# ESP32_zigbee_zwave1.net
KiCad netlist of a schematic drawn in EAGLE
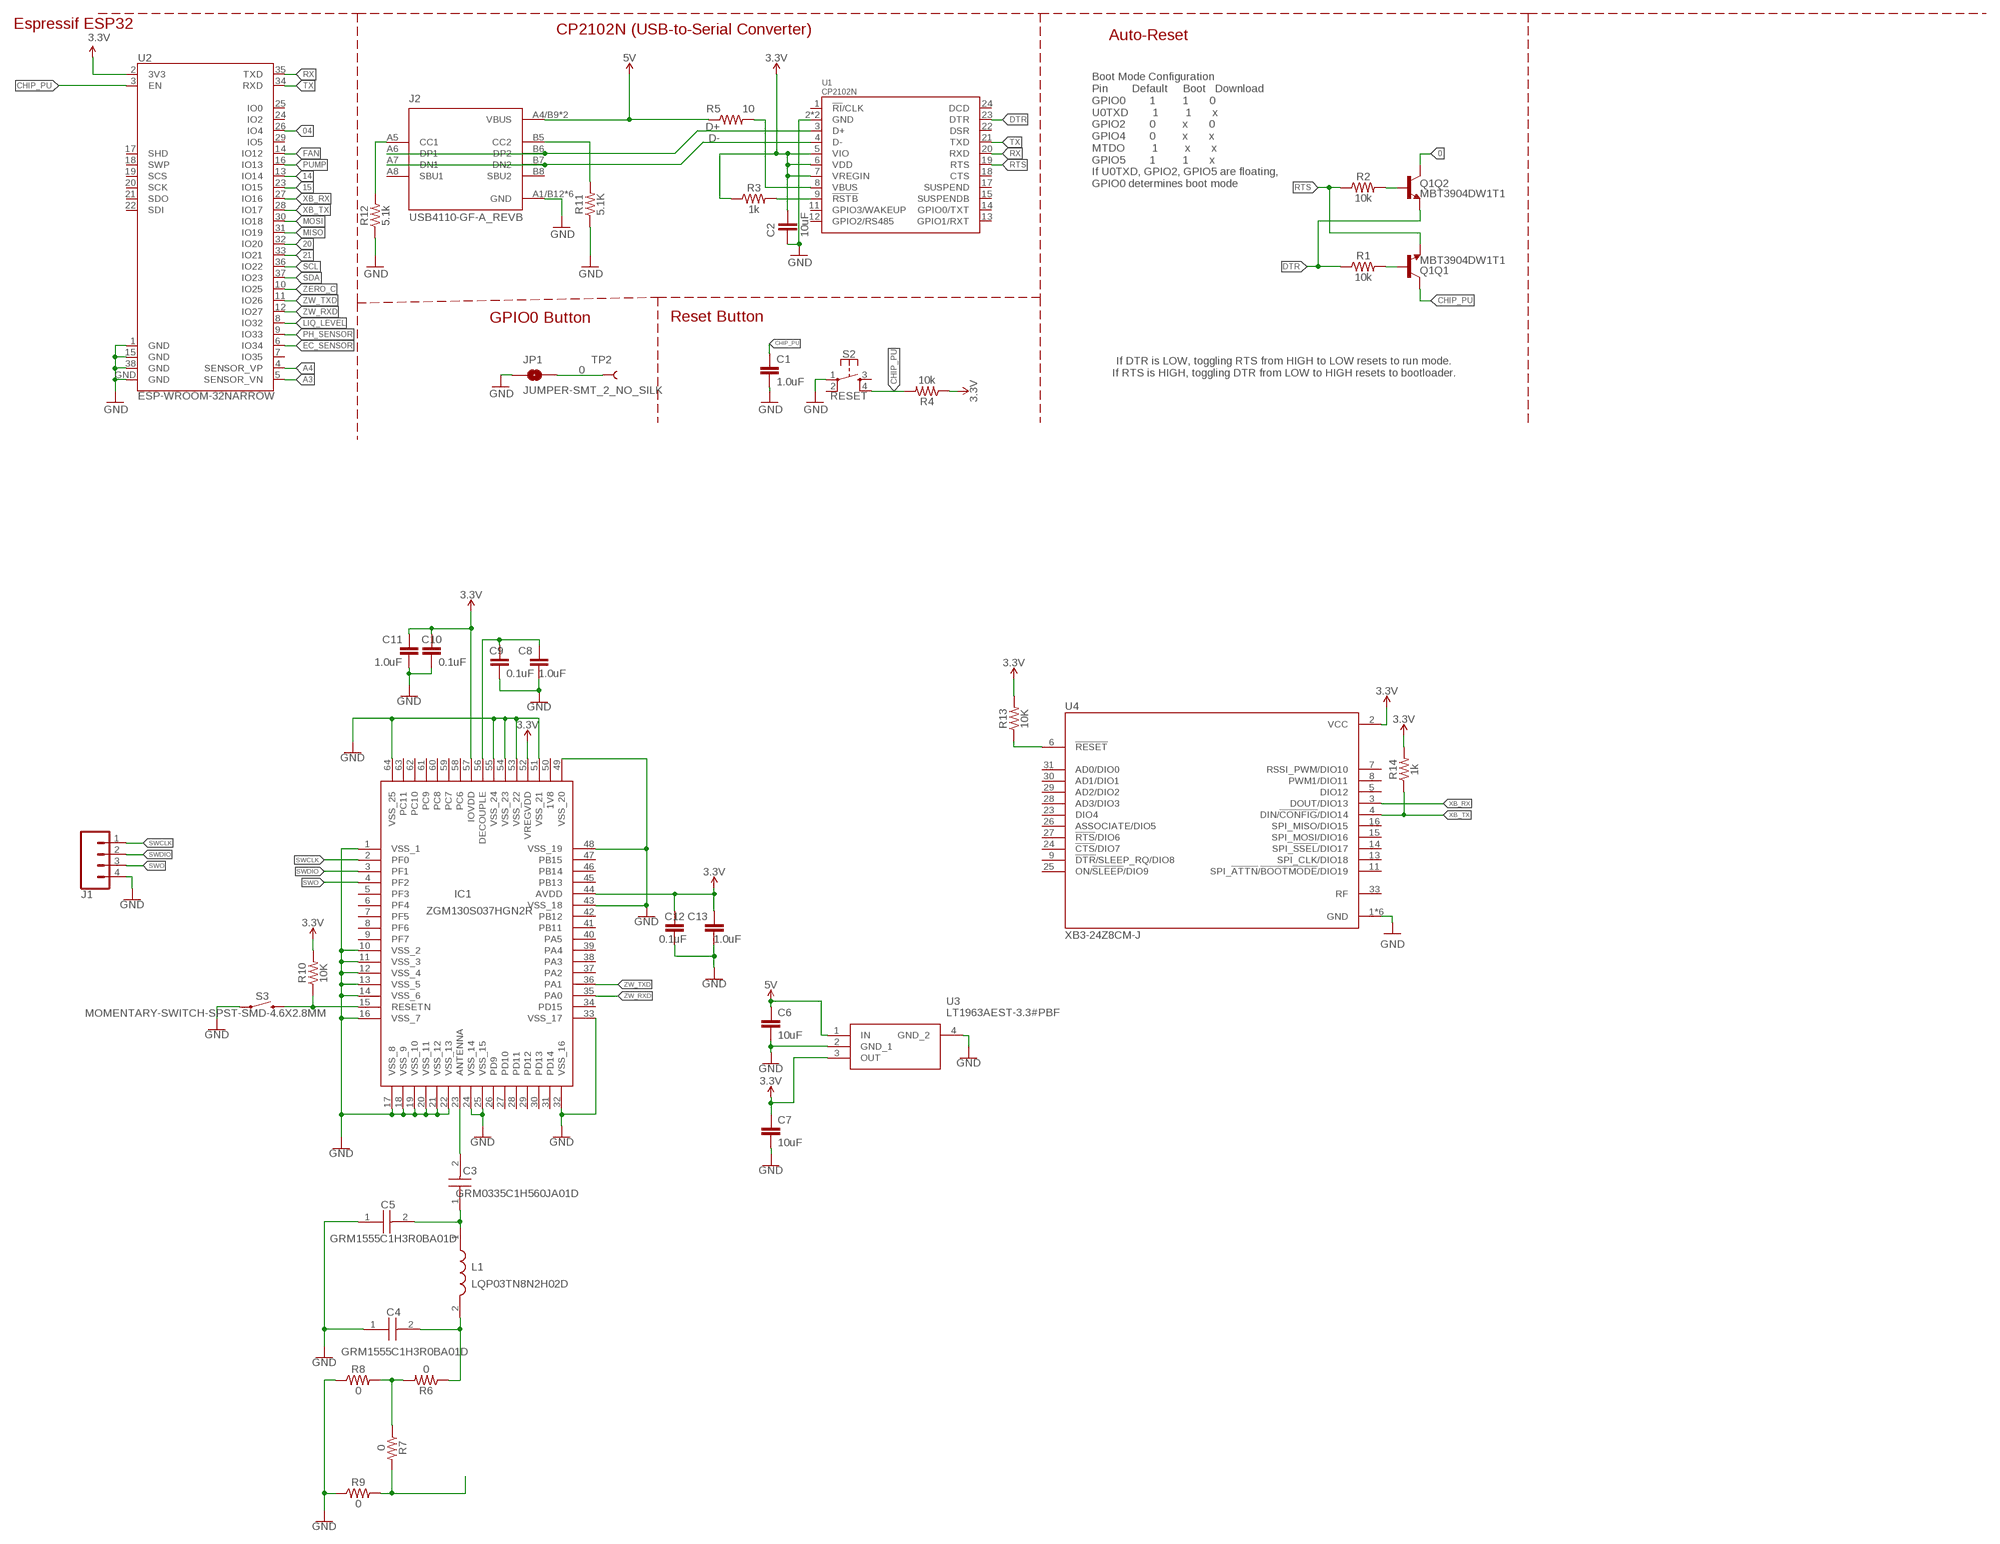
[diagram p0: schematic, sheet 1]

(export (version "E")
  (design (tool "Eeschema 10.0.6"))
  (components
    (comp (ref "C1")
      (value "1.0uF")
      (footprint "eagle-import:0402-TIGHT")
      (libsource (lib "eagle-import") (part "1.0UF-0402T-16V-10%"))
    )
    (comp (ref "C2")
      (value "10uF")
      (footprint "eagle-import:0402-TIGHT")
      (libsource (lib "eagle-import") (part "10UF-0402T-6.3V-20%"))
    )
    (comp (ref "C3")
      (value "GRM0335C1H560JA01D")
      (footprint "eagle-import:CAPC0603X33N")
      (fields (field (name "MOUSER_PART_NUMBER") "81-GRM0335C1H560JA1D"))
      (libsource (lib "eagle-import") (part "GRM0335C1H560JA01D"))
    )
    (comp (ref "C4")
      (value "GRM1555C1H3R0BA01D")
      (footprint "eagle-import:CAPC1005X55N")
      (fields (field (name "MOUSER_PART_NUMBER") "81-GRM1555C1H3R0BA1D"))
      (libsource (lib "eagle-import") (part "GRM1555C1H3R0BA01D"))
    )
    (comp (ref "C5")
      (value "GRM1555C1H3R0BA01D")
      (footprint "eagle-import:CAPC1005X55N")
      (fields (field (name "MOUSER_PART_NUMBER") "81-GRM1555C1H3R0BA1D"))
      (libsource (lib "eagle-import") (part "GRM1555C1H3R0BA01D"))
    )
    (comp (ref "C6")
      (value "10uF")
      (footprint "eagle-import:0402-TIGHT")
      (libsource (lib "eagle-import") (part "10UF-0402T-6.3V-20%"))
    )
    (comp (ref "C7")
      (value "10uF")
      (footprint "eagle-import:0402-TIGHT")
      (libsource (lib "eagle-import") (part "10UF-0402T-6.3V-20%"))
    )
    (comp (ref "C8")
      (value "1.0uF")
      (footprint "eagle-import:0402-TIGHT")
      (libsource (lib "eagle-import") (part "1.0UF-0402T-16V-10%"))
    )
    (comp (ref "C9")
      (value "0.1uF")
      (footprint "eagle-import:0402-TIGHT")
      (libsource (lib "eagle-import") (part "0.1UF-0402T-6.3V-10%-X7R"))
    )
    (comp (ref "C10")
      (value "0.1uF")
      (footprint "eagle-import:0402-TIGHT")
      (libsource (lib "eagle-import") (part "0.1UF-0402T-6.3V-10%-X7R"))
    )
    (comp (ref "C11")
      (value "1.0uF")
      (footprint "eagle-import:0402-TIGHT")
      (libsource (lib "eagle-import") (part "1.0UF-0402T-16V-10%"))
    )
    (comp (ref "C12")
      (value "0.1uF")
      (footprint "eagle-import:0402-TIGHT")
      (libsource (lib "eagle-import") (part "0.1UF-0402T-6.3V-10%-X7R"))
    )
    (comp (ref "C13")
      (value "1.0uF")
      (footprint "eagle-import:0402-TIGHT")
      (libsource (lib "eagle-import") (part "1.0UF-0402T-16V-10%"))
    )
    (comp (ref "IC1")
      (value "ZGM130S037HGN2R")
      (footprint "eagle-import:ZGM130S037HGN2R")
      (fields (field (name "MOUSER_PART_NUMBER") "634-ZGM130S037HGN2R"))
      (libsource (lib "eagle-import") (part "ZGM130S037HGN2R"))
    )
    (comp (ref "J1")
      (value "CONN_041X04_NO_SILK")
      (footprint "eagle-import:1X04_NO_SILK")
      (libsource (lib "eagle-import") (part "CONN_041X04_NO_SILK"))
    )
    (comp (ref "J2")
      (value "USB4110-GF-A_REVB")
      (footprint "eagle-import:GCT_USB4110-GF-A_REVB")
      (fields (field (name "MF") "GCT") (field (name "MP") "USB4110-GF-A"))
      (libsource (lib "eagle-import") (part "USB4110-GF-A_REVB"))
    )
    (comp (ref "JP1")
      (value "JUMPER-SMT_2_NO_SILK")
      (footprint "eagle-import:SMT-JUMPER_2_NO_SILK")
      (libsource (lib "eagle-import") (part "JUMPER-SMT_2_NO_SILK"))
    )
    (comp (ref "L1")
      (value "LQP03TN8N2H02D")
      (footprint "eagle-import:LQP03TG3N1B02D")
      (fields (field (name "MOUSER_PART_NUMBER") "81-LQP03TN8N2H02D"))
      (libsource (lib "eagle-import") (part "LQP03TN8N2H02D"))
    )
    (comp (ref "Q1")
      (value "MBT3904DW1T1")
      (footprint "eagle-import:SC70-6")
      (libsource (lib "eagle-import") (part "TRANS_NPN_DUAL-MBT3904DW1T1"))
    )
    (comp (ref "R1")
      (value "10k")
      (footprint "eagle-import:0402-TIGHT")
      (libsource (lib "eagle-import") (part "10KOHM-0402T-1/16W-1%"))
    )
    (comp (ref "R2")
      (value "10k")
      (footprint "eagle-import:0402-TIGHT")
      (libsource (lib "eagle-import") (part "10KOHM-0402T-1/16W-1%"))
    )
    (comp (ref "R3")
      (value "1k")
      (footprint "eagle-import:0402-TIGHT")
      (libsource (lib "eagle-import") (part "1KOHM-0402T-1/16W-1%"))
    )
    (comp (ref "R4")
      (value "10k")
      (footprint "eagle-import:0402-TIGHT")
      (libsource (lib "eagle-import") (part "10KOHM-0402T-1/16W-1%"))
    )
    (comp (ref "R5")
      (value "10")
      (footprint "eagle-import:0603")
      (libsource (lib "eagle-import") (part "10OHM-0603-1/10W-1%"))
    )
    (comp (ref "R6")
      (value "0")
      (footprint "eagle-import:0402-TIGHT")
      (libsource (lib "eagle-import") (part "0OHM-0402T-1/10W"))
    )
    (comp (ref "R7")
      (value "0")
      (footprint "eagle-import:0402-TIGHT")
      (libsource (lib "eagle-import") (part "0OHM-0402T-1/10W"))
    )
    (comp (ref "R8")
      (value "0")
      (footprint "eagle-import:0402-TIGHT")
      (libsource (lib "eagle-import") (part "0OHM-0402T-1/10W"))
    )
    (comp (ref "R9")
      (value "0")
      (footprint "eagle-import:0402-TIGHT")
      (libsource (lib "eagle-import") (part "0OHM-0402T-1/10W"))
    )
    (comp (ref "R10")
      (value "10K")
      (footprint "eagle-import:0402-TIGHT")
      (libsource (lib "eagle-import") (part "10KOHM-0402-1/10W-0.1%"))
    )
    (comp (ref "R11")
      (value "5.1K")
      (footprint "eagle-import:0402-TIGHT")
      (libsource (lib "eagle-import") (part "RESISTOR0402T"))
    )
    (comp (ref "R12")
      (value "5.1k")
      (footprint "eagle-import:0402-TIGHT")
      (libsource (lib "eagle-import") (part "RESISTOR0402T"))
    )
    (comp (ref "R13")
      (value "10K")
      (footprint "eagle-import:0402-TIGHT")
      (libsource (lib "eagle-import") (part "10KOHM-0402-1/10W-0.1%"))
    )
    (comp (ref "R14")
      (value "1k")
      (footprint "eagle-import:0402-TIGHT")
      (libsource (lib "eagle-import") (part "1KOHM-0402T-1/16W-1%"))
    )
    (comp (ref "S2")
      (value "RESET")
      (footprint "eagle-import:TACTILE_SWITCH_SMD_4.6X2.8MM")
      (libsource (lib "eagle-import") (part "MOMENTARY-SWITCH-SPST-2-SMD-4.6X2.8MM"))
    )
    (comp (ref "S3")
      (value "MOMENTARY-SWITCH-SPST-SMD-4.6X2.8MM")
      (footprint "eagle-import:TACTILE_SWITCH_SMD_4.6X2.8MM")
      (libsource (lib "eagle-import") (part "MOMENTARY-SWITCH-SPST-SMD-4.6X2.8MM"))
    )
    (comp (ref "TP2")
      (value "TEST-POINTTP_15TH_THRU")
      (footprint "eagle-import:TP_15TH")
      (libsource (lib "eagle-import") (part "TEST-POINTTP_15TH_THRU"))
    )
    (comp (ref "U1")
      (value "CP2102N")
      (footprint "eagle-import:QFN24")
      (libsource (lib "eagle-import") (part "CP2102N"))
    )
    (comp (ref "U2")
      (value "ESP-WROOM-32NARROW")
      (footprint "eagle-import:ESP-WROOM-32-NARROW")
      (libsource (lib "eagle-import") (part "ESP-WROOM-32NARROW"))
    )
    (comp (ref "U3")
      (value "LT1963AEST-3.3#PBF")
      (footprint "eagle-import:SOT230P700X180-4N")
      (fields (field (name "MOUSER_PART_NUMBER") "584-1963AEST-3.3PBF"))
      (libsource (lib "eagle-import") (part "LT1963AEST-3.3#PBF"))
    )
    (comp (ref "U4")
      (value "XB3-24Z8CM-J")
      (footprint "eagle-import:XCVR_XB3-24Z8CM-J")
      (fields (field (name "MF") "Digi International"))
      (libsource (lib "eagle-import") (part "XB3-24Z8CM-J"))
    )
  )
  (nets
    (net (code "1") (name "/D+") (class "Default")
      (node (ref "J2") (pin "A6") (pinfunction "DP1_A6") (pintype "bidirectional"))
      (node (ref "J2") (pin "B6") (pinfunction "DP2_B6") (pintype "bidirectional"))
      (node (ref "U1") (pin "3") (pinfunction "D+_3") (pintype "bidirectional"))
    )
    (net (code "2") (name "/D-") (class "Default")
      (node (ref "J2") (pin "A7") (pinfunction "DN1_A7") (pintype "bidirectional"))
      (node (ref "J2") (pin "B7") (pinfunction "DN2_B7") (pintype "bidirectional"))
      (node (ref "U1") (pin "4") (pinfunction "D-_4") (pintype "bidirectional"))
    )
    (net (code "3") (name "0") (class "Default")
      (node (ref "JP1") (pin "2") (pinfunction "2_2") (pintype "passive"))
      (node (ref "Q1") (pin "6") (pinfunction "C_6") (pintype "passive"))
      (node (ref "TP2") (pin "P$1") (pinfunction "1_P$1") (pintype "bidirectional"))
    )
    (net (code "4") (name "3.3V") (class "Default")
      (node (ref "C10") (pin "1") (pinfunction "1_1") (pintype "passive"))
      (node (ref "C11") (pin "2") (pinfunction "2_2") (pintype "passive"))
      (node (ref "C12") (pin "1") (pinfunction "1_1") (pintype "passive"))
      (node (ref "C13") (pin "2") (pinfunction "2_2") (pintype "passive"))
      (node (ref "C2") (pin "1") (pinfunction "1_1") (pintype "passive"))
      (node (ref "C7") (pin "1") (pinfunction "1_1") (pintype "passive"))
      (node (ref "IC1") (pin "44") (pinfunction "AVDD_44") (pintype "bidirectional"))
      (node (ref "IC1") (pin "52") (pinfunction "VREGVDD_52") (pintype "bidirectional"))
      (node (ref "IC1") (pin "57") (pinfunction "IOVDD_57") (pintype "bidirectional"))
      (node (ref "R10") (pin "2") (pinfunction "2_2") (pintype "passive"))
      (node (ref "R13") (pin "2") (pinfunction "2_2") (pintype "passive"))
      (node (ref "R14") (pin "2") (pinfunction "2_2") (pintype "passive"))
      (node (ref "R3") (pin "1") (pinfunction "1_1") (pintype "passive"))
      (node (ref "R4") (pin "1") (pinfunction "1_1") (pintype "passive"))
      (node (ref "U1") (pin "5") (pinfunction "VIO_5") (pintype "bidirectional"))
      (node (ref "U1") (pin "6") (pinfunction "VDD_6") (pintype "bidirectional"))
      (node (ref "U1") (pin "7") (pinfunction "VREGIN_7") (pintype "bidirectional"))
      (node (ref "U2") (pin "2") (pinfunction "3V3_2") (pintype "bidirectional"))
      (node (ref "U3") (pin "3") (pinfunction "OUT_3") (pintype "bidirectional"))
      (node (ref "U4") (pin "2") (pinfunction "VCC_2") (pintype "power_in"))
    )
    (net (code "5") (name "04") (class "Default")
      (node (ref "U2") (pin "26") (pinfunction "IO4_26") (pintype "bidirectional"))
    )
    (net (code "6") (name "5V") (class "Default")
      (node (ref "C6") (pin "1") (pinfunction "1_1") (pintype "passive"))
      (node (ref "J2") (pin "A4/B9") (pinfunction "VBUS_A4/B9") (pintype "power_in"))
      (node (ref "J2") (pin "B4/A9") (pinfunction "VBUS_B4/A9") (pintype "power_in"))
      (node (ref "R5") (pin "1") (pinfunction "1_1") (pintype "passive"))
      (node (ref "U3") (pin "1") (pinfunction "IN_1") (pintype "bidirectional"))
    )
    (net (code "7") (name "14") (class "Default")
      (node (ref "U2") (pin "13") (pinfunction "IO14_13") (pintype "bidirectional"))
    )
    (net (code "8") (name "15") (class "Default")
      (node (ref "U2") (pin "23") (pinfunction "IO15_23") (pintype "bidirectional"))
    )
    (net (code "9") (name "20") (class "Default")
      (node (ref "U2") (pin "32") (pinfunction "IO20_32") (pintype "bidirectional"))
    )
    (net (code "10") (name "21") (class "Default")
      (node (ref "U2") (pin "33") (pinfunction "IO21_33") (pintype "bidirectional"))
    )
    (net (code "11") (name "A3") (class "Default")
      (node (ref "U2") (pin "5") (pinfunction "SENSOR_VN_5") (pintype "bidirectional"))
    )
    (net (code "12") (name "A4") (class "Default")
      (node (ref "U2") (pin "4") (pinfunction "SENSOR_VP_4") (pintype "bidirectional"))
    )
    (net (code "13") (name "CHIP_PU") (class "Default")
      (node (ref "C1") (pin "1") (pinfunction "1_1") (pintype "passive"))
      (node (ref "Q1") (pin "3") (pinfunction "C_3") (pintype "passive"))
      (node (ref "R4") (pin "2") (pinfunction "2_2") (pintype "passive"))
      (node (ref "S2") (pin "4") (pinfunction "4_4") (pintype "passive"))
      (node (ref "U2") (pin "3") (pinfunction "EN_3") (pintype "bidirectional"))
    )
    (net (code "14") (name "DTR") (class "Default")
      (node (ref "Q1") (pin "1") (pinfunction "E_1") (pintype "passive"))
      (node (ref "R1") (pin "1") (pinfunction "1_1") (pintype "passive"))
      (node (ref "U1") (pin "23") (pinfunction "DTR_23") (pintype "bidirectional"))
    )
    (net (code "15") (name "EC_SENSOR") (class "Default")
      (node (ref "U2") (pin "6") (pinfunction "IO34_6") (pintype "bidirectional"))
    )
    (net (code "16") (name "FAN") (class "Default")
      (node (ref "U2") (pin "14") (pinfunction "IO12_14") (pintype "bidirectional"))
    )
    (net (code "17") (name "GND") (class "Default")
      (node (ref "C1") (pin "2") (pinfunction "2_2") (pintype "passive"))
      (node (ref "C10") (pin "2") (pinfunction "2_2") (pintype "passive"))
      (node (ref "C11") (pin "1") (pinfunction "1_1") (pintype "passive"))
      (node (ref "C12") (pin "2") (pinfunction "2_2") (pintype "passive"))
      (node (ref "C13") (pin "1") (pinfunction "1_1") (pintype "passive"))
      (node (ref "C2") (pin "2") (pinfunction "2_2") (pintype "passive"))
      (node (ref "C4") (pin "1") (pinfunction "1_1") (pintype "bidirectional"))
      (node (ref "C5") (pin "1") (pinfunction "1_1") (pintype "bidirectional"))
      (node (ref "C6") (pin "2") (pinfunction "2_2") (pintype "passive"))
      (node (ref "C7") (pin "2") (pinfunction "2_2") (pintype "passive"))
      (node (ref "C8") (pin "1") (pinfunction "1_1") (pintype "passive"))
      (node (ref "C9") (pin "2") (pinfunction "2_2") (pintype "passive"))
      (node (ref "IC1") (pin "1") (pinfunction "VSS_1_1") (pintype "bidirectional"))
      (node (ref "IC1") (pin "10") (pinfunction "VSS_2_10") (pintype "bidirectional"))
      (node (ref "IC1") (pin "11") (pinfunction "VSS_3_11") (pintype "bidirectional"))
      (node (ref "IC1") (pin "12") (pinfunction "VSS_4_12") (pintype "bidirectional"))
      (node (ref "IC1") (pin "13") (pinfunction "VSS_5_13") (pintype "bidirectional"))
      (node (ref "IC1") (pin "14") (pinfunction "VSS_6_14") (pintype "bidirectional"))
      (node (ref "IC1") (pin "16") (pinfunction "VSS_7_16") (pintype "bidirectional"))
      (node (ref "IC1") (pin "17") (pinfunction "VSS_8_17") (pintype "bidirectional"))
      (node (ref "IC1") (pin "18") (pinfunction "VSS_9_18") (pintype "bidirectional"))
      (node (ref "IC1") (pin "19") (pinfunction "VSS_10_19") (pintype "bidirectional"))
      (node (ref "IC1") (pin "20") (pinfunction "VSS_11_20") (pintype "bidirectional"))
      (node (ref "IC1") (pin "21") (pinfunction "VSS_12_21") (pintype "bidirectional"))
      (node (ref "IC1") (pin "22") (pinfunction "VSS_13_22") (pintype "bidirectional"))
      (node (ref "IC1") (pin "24") (pinfunction "VSS_14_24") (pintype "bidirectional"))
      (node (ref "IC1") (pin "25") (pinfunction "VSS_15_25") (pintype "bidirectional"))
      (node (ref "IC1") (pin "32") (pinfunction "VSS_16_32") (pintype "bidirectional"))
      (node (ref "IC1") (pin "33") (pinfunction "VSS_17_33") (pintype "bidirectional"))
      (node (ref "IC1") (pin "43") (pinfunction "VSS_18_43") (pintype "bidirectional"))
      (node (ref "IC1") (pin "48") (pinfunction "VSS_19_48") (pintype "bidirectional"))
      (node (ref "IC1") (pin "49") (pinfunction "VSS_20_49") (pintype "bidirectional"))
      (node (ref "IC1") (pin "51") (pinfunction "VSS_21_51") (pintype "bidirectional"))
      (node (ref "IC1") (pin "53") (pinfunction "VSS_22_53") (pintype "bidirectional"))
      (node (ref "IC1") (pin "54") (pinfunction "VSS_23_54") (pintype "bidirectional"))
      (node (ref "IC1") (pin "55") (pinfunction "VSS_24_55") (pintype "bidirectional"))
      (node (ref "IC1") (pin "64") (pinfunction "VSS_25_64") (pintype "bidirectional"))
      (node (ref "J1") (pin "4") (pinfunction "4_4") (pintype "passive"))
      (node (ref "J2") (pin "A1/B12") (pinfunction "GND_A1/B12") (pintype "power_in"))
      (node (ref "J2") (pin "B1/A12") (pinfunction "GND_B1/A12") (pintype "power_in"))
      (node (ref "J2") (pin "S1") (pinfunction "GND_S1") (pintype "power_in"))
      (node (ref "J2") (pin "S2") (pinfunction "GND_S2") (pintype "power_in"))
      (node (ref "J2") (pin "S3") (pinfunction "GND_S3") (pintype "power_in"))
      (node (ref "J2") (pin "S4") (pinfunction "GND_S4") (pintype "power_in"))
      (node (ref "JP1") (pin "1") (pinfunction "1_1") (pintype "passive"))
      (node (ref "R11") (pin "1") (pinfunction "1_1") (pintype "passive"))
      (node (ref "R12") (pin "1") (pinfunction "1_1") (pintype "passive"))
      (node (ref "R8") (pin "1") (pinfunction "1_1") (pintype "passive"))
      (node (ref "R9") (pin "1") (pinfunction "1_1") (pintype "passive"))
      (node (ref "S2") (pin "1") (pinfunction "1_1") (pintype "passive"))
      (node (ref "S3") (pin "1") (pinfunction "1_1") (pintype "passive"))
      (node (ref "S3") (pin "2") (pinfunction "1_2") (pintype "passive"))
      (node (ref "U1") (pin "2") (pinfunction "GND_2") (pintype "bidirectional"))
      (node (ref "U1") (pin "PAD") (pinfunction "GND_PAD") (pintype "bidirectional"))
      (node (ref "U2") (pin "1") (pinfunction "GND_1") (pintype "bidirectional"))
      (node (ref "U2") (pin "15") (pinfunction "GND_15") (pintype "bidirectional"))
      (node (ref "U2") (pin "38") (pinfunction "GND_38") (pintype "bidirectional"))
      (node (ref "U2") (pin "GND") (pinfunction "GND_GND") (pintype "bidirectional"))
      (node (ref "U3") (pin "2") (pinfunction "GND_1_2") (pintype "bidirectional"))
      (node (ref "U3") (pin "4") (pinfunction "GND_2_4") (pintype "bidirectional"))
      (node (ref "U4") (pin "1") (pinfunction "GND_1") (pintype "power_in"))
      (node (ref "U4") (pin "10") (pinfunction "GND_10") (pintype "power_in"))
      (node (ref "U4") (pin "12") (pinfunction "GND_12") (pintype "power_in"))
      (node (ref "U4") (pin "21") (pinfunction "GND_21") (pintype "power_in"))
      (node (ref "U4") (pin "32") (pinfunction "GND_32") (pintype "power_in"))
      (node (ref "U4") (pin "34") (pinfunction "GND_34") (pintype "power_in"))
    )
    (net (code "18") (name "LIQ_LEVEL") (class "Default")
      (node (ref "U2") (pin "8") (pinfunction "IO32_8") (pintype "bidirectional"))
    )
    (net (code "19") (name "MISO") (class "Default")
      (node (ref "U2") (pin "31") (pinfunction "IO19_31") (pintype "bidirectional"))
    )
    (net (code "20") (name "MOSI") (class "Default")
      (node (ref "U2") (pin "30") (pinfunction "IO18_30") (pintype "bidirectional"))
    )
    (net (code "21") (name "Net-(C3-Pad1)") (class "Default")
      (node (ref "C3") (pin "1") (pinfunction "1_1") (pintype "bidirectional"))
      (node (ref "C5") (pin "2") (pinfunction "2_2") (pintype "bidirectional"))
      (node (ref "L1") (pin "1") (pinfunction "1_1") (pintype "bidirectional"))
    )
    (net (code "22") (name "Net-(C4-Pad2)") (class "Default")
      (node (ref "C4") (pin "2") (pinfunction "2_2") (pintype "bidirectional"))
      (node (ref "L1") (pin "2") (pinfunction "2_2") (pintype "bidirectional"))
      (node (ref "R6") (pin "1") (pinfunction "1_1") (pintype "passive"))
    )
    (net (code "23") (name "Net-(IC1-ANTENNA)") (class "Default")
      (node (ref "C3") (pin "2") (pinfunction "2_2") (pintype "bidirectional"))
      (node (ref "IC1") (pin "23") (pinfunction "ANTENNA_23") (pintype "bidirectional"))
    )
    (net (code "24") (name "Net-(IC1-DECOUPLE)") (class "Default")
      (node (ref "C8") (pin "2") (pinfunction "2_2") (pintype "passive"))
      (node (ref "C9") (pin "1") (pinfunction "1_1") (pintype "passive"))
      (node (ref "IC1") (pin "56") (pinfunction "DECOUPLE_56") (pintype "bidirectional"))
    )
    (net (code "25") (name "Net-(IC1-RESETN)") (class "Default")
      (node (ref "IC1") (pin "15") (pinfunction "RESETN_15") (pintype "bidirectional"))
      (node (ref "R10") (pin "1") (pinfunction "1_1") (pintype "passive"))
      (node (ref "S3") (pin "3") (pinfunction "2_3") (pintype "passive"))
      (node (ref "S3") (pin "4") (pinfunction "2_4") (pintype "passive"))
    )
    (net (code "26") (name "Net-(J2-CC1)") (class "Default")
      (node (ref "J2") (pin "A5") (pinfunction "CC1_A5") (pintype "bidirectional"))
      (node (ref "R12") (pin "2") (pinfunction "2_2") (pintype "passive"))
    )
    (net (code "27") (name "Net-(J2-CC2)") (class "Default")
      (node (ref "J2") (pin "B5") (pinfunction "CC2_B5") (pintype "bidirectional"))
      (node (ref "R11") (pin "2") (pinfunction "2_2") (pintype "passive"))
    )
    (net (code "28") (name "Net-(Q1A-B)") (class "Default")
      (node (ref "Q1") (pin "5") (pinfunction "B_5") (pintype "passive"))
      (node (ref "R1") (pin "2") (pinfunction "2_2") (pintype "passive"))
    )
    (net (code "29") (name "Net-(Q1B-B)") (class "Default")
      (node (ref "Q1") (pin "2") (pinfunction "B_2") (pintype "passive"))
      (node (ref "R2") (pin "2") (pinfunction "2_2") (pintype "passive"))
    )
    (net (code "30") (name "Net-(R6-Pad2)") (class "Default")
      (node (ref "R6") (pin "2") (pinfunction "2_2") (pintype "passive"))
      (node (ref "R7") (pin "1") (pinfunction "1_1") (pintype "passive"))
      (node (ref "R8") (pin "2") (pinfunction "2_2") (pintype "passive"))
    )
    (net (code "31") (name "Net-(R7-Pad2)") (class "Default")
      (node (ref "R7") (pin "2") (pinfunction "2_2") (pintype "passive"))
      (node (ref "R9") (pin "2") (pinfunction "2_2") (pintype "passive"))
    )
    (net (code "32") (name "Net-(U1-VBUS)") (class "Default")
      (node (ref "R5") (pin "2") (pinfunction "2_2") (pintype "passive"))
      (node (ref "U1") (pin "8") (pinfunction "VBUS_8") (pintype "bidirectional"))
    )
    (net (code "33") (name "Net-(U1-~{RSTB})") (class "Default")
      (node (ref "R3") (pin "2") (pinfunction "2_2") (pintype "passive"))
      (node (ref "U1") (pin "9") (pinfunction "~{RSTB}_9") (pintype "bidirectional"))
    )
    (net (code "34") (name "Net-(U4-~{RESET})") (class "Default")
      (node (ref "R13") (pin "1") (pinfunction "1_1") (pintype "passive"))
      (node (ref "U4") (pin "6") (pinfunction "~{RESET}_6") (pintype "input"))
    )
    (net (code "35") (name "PH_SENSOR") (class "Default")
      (node (ref "U2") (pin "9") (pinfunction "IO33_9") (pintype "bidirectional"))
    )
    (net (code "36") (name "PUMP") (class "Default")
      (node (ref "U2") (pin "16") (pinfunction "IO13_16") (pintype "bidirectional"))
    )
    (net (code "37") (name "RTS") (class "Default")
      (node (ref "Q1") (pin "4") (pinfunction "E_4") (pintype "passive"))
      (node (ref "R2") (pin "1") (pinfunction "1_1") (pintype "passive"))
      (node (ref "U1") (pin "19") (pinfunction "RTS_19") (pintype "bidirectional"))
    )
    (net (code "38") (name "RX") (class "Default")
      (node (ref "U1") (pin "20") (pinfunction "RXD_20") (pintype "bidirectional"))
      (node (ref "U2") (pin "35") (pinfunction "TXD_35") (pintype "bidirectional"))
    )
    (net (code "39") (name "SCL") (class "Default")
      (node (ref "U2") (pin "36") (pinfunction "IO22_36") (pintype "bidirectional"))
    )
    (net (code "40") (name "SDA") (class "Default")
      (node (ref "U2") (pin "37") (pinfunction "IO23_37") (pintype "bidirectional"))
    )
    (net (code "41") (name "SWCLK") (class "Default")
      (node (ref "IC1") (pin "2") (pinfunction "PF0_2") (pintype "bidirectional"))
      (node (ref "J1") (pin "1") (pinfunction "1_1") (pintype "passive"))
    )
    (net (code "42") (name "SWDIO") (class "Default")
      (node (ref "IC1") (pin "3") (pinfunction "PF1_3") (pintype "bidirectional"))
      (node (ref "J1") (pin "2") (pinfunction "2_2") (pintype "passive"))
    )
    (net (code "43") (name "SWO") (class "Default")
      (node (ref "IC1") (pin "4") (pinfunction "PF2_4") (pintype "bidirectional"))
      (node (ref "J1") (pin "3") (pinfunction "3_3") (pintype "passive"))
    )
    (net (code "44") (name "TX") (class "Default")
      (node (ref "U1") (pin "21") (pinfunction "TXD_21") (pintype "bidirectional"))
      (node (ref "U2") (pin "34") (pinfunction "RXD_34") (pintype "bidirectional"))
    )
    (net (code "45") (name "XB_RX") (class "Default")
      (node (ref "U2") (pin "27") (pinfunction "IO16_27") (pintype "bidirectional"))
      (node (ref "U4") (pin "3") (pinfunction "DOUT/DIO13_3") (pintype "bidirectional"))
    )
    (net (code "46") (name "XB_TX") (class "Default")
      (node (ref "R14") (pin "1") (pinfunction "1_1") (pintype "passive"))
      (node (ref "U2") (pin "28") (pinfunction "IO17_28") (pintype "bidirectional"))
      (node (ref "U4") (pin "4") (pinfunction "DIN/~{CONFIG}/DIO14_4") (pintype "bidirectional"))
    )
    (net (code "47") (name "ZERO_C") (class "Default")
      (node (ref "U2") (pin "10") (pinfunction "IO25_10") (pintype "bidirectional"))
    )
    (net (code "48") (name "ZW_RXD") (class "Default")
      (node (ref "IC1") (pin "35") (pinfunction "PA0_35") (pintype "bidirectional"))
      (node (ref "U2") (pin "12") (pinfunction "IO27_12") (pintype "bidirectional"))
    )
    (net (code "49") (name "ZW_TXD") (class "Default")
      (node (ref "IC1") (pin "36") (pinfunction "PA1_36") (pintype "bidirectional"))
      (node (ref "U2") (pin "11") (pinfunction "IO26_11") (pintype "bidirectional"))
    )
    (net (code "50") (name "unconnected-(IC1-1V8-Pad50)") (class "Default")
      (node (ref "IC1") (pin "50") (pinfunction "1V8_50") (pintype "bidirectional"))
    )
    (net (code "51") (name "unconnected-(IC1-PA2-Pad37)") (class "Default")
      (node (ref "IC1") (pin "37") (pinfunction "PA2_37") (pintype "bidirectional"))
    )
    (net (code "52") (name "unconnected-(IC1-PA3-Pad38)") (class "Default")
      (node (ref "IC1") (pin "38") (pinfunction "PA3_38") (pintype "bidirectional"))
    )
    (net (code "53") (name "unconnected-(IC1-PA4-Pad39)") (class "Default")
      (node (ref "IC1") (pin "39") (pinfunction "PA4_39") (pintype "bidirectional"))
    )
    (net (code "54") (name "unconnected-(IC1-PA5-Pad40)") (class "Default")
      (node (ref "IC1") (pin "40") (pinfunction "PA5_40") (pintype "bidirectional"))
    )
    (net (code "55") (name "unconnected-(IC1-PB11-Pad41)") (class "Default")
      (node (ref "IC1") (pin "41") (pinfunction "PB11_41") (pintype "bidirectional"))
    )
    (net (code "56") (name "unconnected-(IC1-PB12-Pad42)") (class "Default")
      (node (ref "IC1") (pin "42") (pinfunction "PB12_42") (pintype "bidirectional"))
    )
    (net (code "57") (name "unconnected-(IC1-PB13-Pad45)") (class "Default")
      (node (ref "IC1") (pin "45") (pinfunction "PB13_45") (pintype "bidirectional"))
    )
    (net (code "58") (name "unconnected-(IC1-PB14-Pad46)") (class "Default")
      (node (ref "IC1") (pin "46") (pinfunction "PB14_46") (pintype "bidirectional"))
    )
    (net (code "59") (name "unconnected-(IC1-PB15-Pad47)") (class "Default")
      (node (ref "IC1") (pin "47") (pinfunction "PB15_47") (pintype "bidirectional"))
    )
    (net (code "60") (name "unconnected-(IC1-PC6-Pad58)") (class "Default")
      (node (ref "IC1") (pin "58") (pinfunction "PC6_58") (pintype "bidirectional"))
    )
    (net (code "61") (name "unconnected-(IC1-PC7-Pad59)") (class "Default")
      (node (ref "IC1") (pin "59") (pinfunction "PC7_59") (pintype "bidirectional"))
    )
    (net (code "62") (name "unconnected-(IC1-PC8-Pad60)") (class "Default")
      (node (ref "IC1") (pin "60") (pinfunction "PC8_60") (pintype "bidirectional"))
    )
    (net (code "63") (name "unconnected-(IC1-PC9-Pad61)") (class "Default")
      (node (ref "IC1") (pin "61") (pinfunction "PC9_61") (pintype "bidirectional"))
    )
    (net (code "64") (name "unconnected-(IC1-PC10-Pad62)") (class "Default")
      (node (ref "IC1") (pin "62") (pinfunction "PC10_62") (pintype "bidirectional"))
    )
    (net (code "65") (name "unconnected-(IC1-PC11-Pad63)") (class "Default")
      (node (ref "IC1") (pin "63") (pinfunction "PC11_63") (pintype "bidirectional"))
    )
    (net (code "66") (name "unconnected-(IC1-PD9-Pad26)") (class "Default")
      (node (ref "IC1") (pin "26") (pinfunction "PD9_26") (pintype "bidirectional"))
    )
    (net (code "67") (name "unconnected-(IC1-PD10-Pad27)") (class "Default")
      (node (ref "IC1") (pin "27") (pinfunction "PD10_27") (pintype "bidirectional"))
    )
    (net (code "68") (name "unconnected-(IC1-PD11-Pad28)") (class "Default")
      (node (ref "IC1") (pin "28") (pinfunction "PD11_28") (pintype "bidirectional"))
    )
    (net (code "69") (name "unconnected-(IC1-PD12-Pad29)") (class "Default")
      (node (ref "IC1") (pin "29") (pinfunction "PD12_29") (pintype "bidirectional"))
    )
    (net (code "70") (name "unconnected-(IC1-PD13-Pad30)") (class "Default")
      (node (ref "IC1") (pin "30") (pinfunction "PD13_30") (pintype "bidirectional"))
    )
    (net (code "71") (name "unconnected-(IC1-PD14-Pad31)") (class "Default")
      (node (ref "IC1") (pin "31") (pinfunction "PD14_31") (pintype "bidirectional"))
    )
    (net (code "72") (name "unconnected-(IC1-PD15-Pad34)") (class "Default")
      (node (ref "IC1") (pin "34") (pinfunction "PD15_34") (pintype "bidirectional"))
    )
    (net (code "73") (name "unconnected-(IC1-PF3-Pad5)") (class "Default")
      (node (ref "IC1") (pin "5") (pinfunction "PF3_5") (pintype "bidirectional"))
    )
    (net (code "74") (name "unconnected-(IC1-PF4-Pad6)") (class "Default")
      (node (ref "IC1") (pin "6") (pinfunction "PF4_6") (pintype "bidirectional"))
    )
    (net (code "75") (name "unconnected-(IC1-PF5-Pad7)") (class "Default")
      (node (ref "IC1") (pin "7") (pinfunction "PF5_7") (pintype "bidirectional"))
    )
    (net (code "76") (name "unconnected-(IC1-PF6-Pad8)") (class "Default")
      (node (ref "IC1") (pin "8") (pinfunction "PF6_8") (pintype "bidirectional"))
    )
    (net (code "77") (name "unconnected-(IC1-PF7-Pad9)") (class "Default")
      (node (ref "IC1") (pin "9") (pinfunction "PF7_9") (pintype "bidirectional"))
    )
    (net (code "78") (name "unconnected-(J2-SBU1-PadA8)") (class "Default")
      (node (ref "J2") (pin "A8") (pinfunction "SBU1_A8") (pintype "bidirectional"))
    )
    (net (code "79") (name "unconnected-(J2-SBU2-PadB8)") (class "Default")
      (node (ref "J2") (pin "B8") (pinfunction "SBU2_B8") (pintype "bidirectional"))
    )
    (net (code "80") (name "unconnected-(S2-Pad2)") (class "Default")
      (node (ref "S2") (pin "2") (pinfunction "2_2") (pintype "passive"))
    )
    (net (code "81") (name "unconnected-(S2-Pad3)") (class "Default")
      (node (ref "S2") (pin "3") (pinfunction "3_3") (pintype "passive"))
    )
    (net (code "82") (name "unconnected-(U1-CTS-Pad18)") (class "Default")
      (node (ref "U1") (pin "18") (pinfunction "CTS_18") (pintype "bidirectional"))
    )
    (net (code "83") (name "unconnected-(U1-DCD-Pad24)") (class "Default")
      (node (ref "U1") (pin "24") (pinfunction "DCD_24") (pintype "bidirectional"))
    )
    (net (code "84") (name "unconnected-(U1-DSR-Pad22)") (class "Default")
      (node (ref "U1") (pin "22") (pinfunction "DSR_22") (pintype "bidirectional"))
    )
    (net (code "85") (name "unconnected-(U1-GPIO0{slash}TXT-Pad14)") (class "Default")
      (node (ref "U1") (pin "14") (pinfunction "GPIO0/TXT_14") (pintype "bidirectional"))
    )
    (net (code "86") (name "unconnected-(U1-GPIO1{slash}RXT-Pad13)") (class "Default")
      (node (ref "U1") (pin "13") (pinfunction "GPIO1/RXT_13") (pintype "bidirectional"))
    )
    (net (code "87") (name "unconnected-(U1-GPIO2{slash}RS485-Pad12)") (class "Default")
      (node (ref "U1") (pin "12") (pinfunction "GPIO2/RS485_12") (pintype "bidirectional"))
    )
    (net (code "88") (name "unconnected-(U1-GPIO3{slash}WAKEUP-Pad11)") (class "Default")
      (node (ref "U1") (pin "11") (pinfunction "GPIO3/WAKEUP_11") (pintype "bidirectional"))
    )
    (net (code "89") (name "unconnected-(U1-SUSPEND-Pad17)") (class "Default")
      (node (ref "U1") (pin "17") (pinfunction "SUSPEND_17") (pintype "bidirectional"))
    )
    (net (code "90") (name "unconnected-(U1-SUSPENDB-Pad15)") (class "Default")
      (node (ref "U1") (pin "15") (pinfunction "SUSPENDB_15") (pintype "bidirectional"))
    )
    (net (code "91") (name "unconnected-(U1-~{RI}{slash}CLK-Pad1)") (class "Default")
      (node (ref "U1") (pin "1") (pinfunction "~{RI}/CLK_1") (pintype "bidirectional"))
    )
    (net (code "92") (name "unconnected-(U2-IO0-Pad25)") (class "Default")
      (node (ref "U2") (pin "25") (pinfunction "IO0_25") (pintype "bidirectional"))
    )
    (net (code "93") (name "unconnected-(U2-IO2-Pad24)") (class "Default")
      (node (ref "U2") (pin "24") (pinfunction "IO2_24") (pintype "bidirectional"))
    )
    (net (code "94") (name "unconnected-(U2-IO5-Pad29)") (class "Default")
      (node (ref "U2") (pin "29") (pinfunction "IO5_29") (pintype "bidirectional"))
    )
    (net (code "95") (name "unconnected-(U2-IO35-Pad7)") (class "Default")
      (node (ref "U2") (pin "7") (pinfunction "IO35_7") (pintype "bidirectional"))
    )
    (net (code "96") (name "unconnected-(U2-SCK-Pad20)") (class "Default")
      (node (ref "U2") (pin "20") (pinfunction "SCK_20") (pintype "bidirectional"))
    )
    (net (code "97") (name "unconnected-(U2-SCS-Pad19)") (class "Default")
      (node (ref "U2") (pin "19") (pinfunction "SCS_19") (pintype "bidirectional"))
    )
    (net (code "98") (name "unconnected-(U2-SDI-Pad22)") (class "Default")
      (node (ref "U2") (pin "22") (pinfunction "SDI_22") (pintype "bidirectional"))
    )
    (net (code "99") (name "unconnected-(U2-SDO-Pad21)") (class "Default")
      (node (ref "U2") (pin "21") (pinfunction "SDO_21") (pintype "bidirectional"))
    )
    (net (code "100") (name "unconnected-(U2-SHD-Pad17)") (class "Default")
      (node (ref "U2") (pin "17") (pinfunction "SHD_17") (pintype "bidirectional"))
    )
    (net (code "101") (name "unconnected-(U2-SWP-Pad18)") (class "Default")
      (node (ref "U2") (pin "18") (pinfunction "SWP_18") (pintype "bidirectional"))
    )
    (net (code "102") (name "unconnected-(U4-AD0{slash}DIO0-Pad31)") (class "Default")
      (node (ref "U4") (pin "31") (pinfunction "AD0/DIO0_31") (pintype "bidirectional"))
    )
    (net (code "103") (name "unconnected-(U4-AD1{slash}DIO1-Pad30)") (class "Default")
      (node (ref "U4") (pin "30") (pinfunction "AD1/DIO1_30") (pintype "bidirectional"))
    )
    (net (code "104") (name "unconnected-(U4-AD2{slash}DIO2-Pad29)") (class "Default")
      (node (ref "U4") (pin "29") (pinfunction "AD2/DIO2_29") (pintype "bidirectional"))
    )
    (net (code "105") (name "unconnected-(U4-AD3{slash}DIO3-Pad28)") (class "Default")
      (node (ref "U4") (pin "28") (pinfunction "AD3/DIO3_28") (pintype "bidirectional"))
    )
    (net (code "106") (name "unconnected-(U4-ASSOCIATE{slash}DIO5-Pad26)") (class "Default")
      (node (ref "U4") (pin "26") (pinfunction "ASSOCIATE/DIO5_26") (pintype "bidirectional"))
    )
    (net (code "107") (name "unconnected-(U4-DIO4-Pad23)") (class "Default")
      (node (ref "U4") (pin "23") (pinfunction "DIO4_23") (pintype "bidirectional"))
    )
    (net (code "108") (name "unconnected-(U4-DIO12-Pad5)") (class "Default")
      (node (ref "U4") (pin "5") (pinfunction "DIO12_5") (pintype "bidirectional"))
    )
    (net (code "109") (name "unconnected-(U4-ON{slash}~{SLEEP}{slash}DIO9-Pad25)") (class "Default")
      (node (ref "U4") (pin "25") (pinfunction "ON/~{SLEEP}/DIO9_25") (pintype "bidirectional"))
    )
    (net (code "110") (name "unconnected-(U4-PWM1{slash}DIO11-Pad8)") (class "Default")
      (node (ref "U4") (pin "8") (pinfunction "PWM1/DIO11_8") (pintype "bidirectional"))
    )
    (net (code "111") (name "unconnected-(U4-RF-Pad33)") (class "Default")
      (node (ref "U4") (pin "33") (pinfunction "RF_33") (pintype "bidirectional"))
    )
    (net (code "112") (name "unconnected-(U4-RSSI_PWM{slash}DIO10-Pad7)") (class "Default")
      (node (ref "U4") (pin "7") (pinfunction "RSSI_PWM/DIO10_7") (pintype "bidirectional"))
    )
    (net (code "113") (name "unconnected-(U4-SPI_CLK{slash}DIO18-Pad13)") (class "Default")
      (node (ref "U4") (pin "13") (pinfunction "SPI_CLK/DIO18_13") (pintype "bidirectional"))
    )
    (net (code "114") (name "unconnected-(U4-SPI_MISO{slash}DIO15-Pad16)") (class "Default")
      (node (ref "U4") (pin "16") (pinfunction "SPI_MISO/DIO15_16") (pintype "bidirectional"))
    )
    (net (code "115") (name "unconnected-(U4-SPI_MOSI{slash}DIO16-Pad15)") (class "Default")
      (node (ref "U4") (pin "15") (pinfunction "SPI_MOSI/DIO16_15") (pintype "bidirectional"))
    )
    (net (code "116") (name "unconnected-(U4-SPI_~{ATTN}{slash}~{BOOTMODE}{slash}DIO19-Pad11)") (class "Default")
      (node (ref "U4") (pin "11") (pinfunction "SPI_~{ATTN}/~{BOOTMODE}/DIO19_11") (pintype "bidirectional"))
    )
    (net (code "117") (name "unconnected-(U4-SPI_~{SSEL}{slash}DIO17-Pad14)") (class "Default")
      (node (ref "U4") (pin "14") (pinfunction "SPI_~{SSEL}/DIO17_14") (pintype "bidirectional"))
    )
    (net (code "118") (name "unconnected-(U4-~{CTS}{slash}DIO7-Pad24)") (class "Default")
      (node (ref "U4") (pin "24") (pinfunction "~{CTS}/DIO7_24") (pintype "bidirectional"))
    )
    (net (code "119") (name "unconnected-(U4-~{DTR}{slash}SLEEP_RQ{slash}DIO8-Pad9)") (class "Default")
      (node (ref "U4") (pin "9") (pinfunction "~{DTR}/SLEEP_RQ/DIO8_9") (pintype "bidirectional"))
    )
    (net (code "120") (name "unconnected-(U4-~{RTS}{slash}DIO6-Pad27)") (class "Default")
      (node (ref "U4") (pin "27") (pinfunction "~{RTS}/DIO6_27") (pintype "bidirectional"))
    )
  )
)
